# SCB_Connectors.net
KiCad netlist of a schematic drawn in Altium Designer
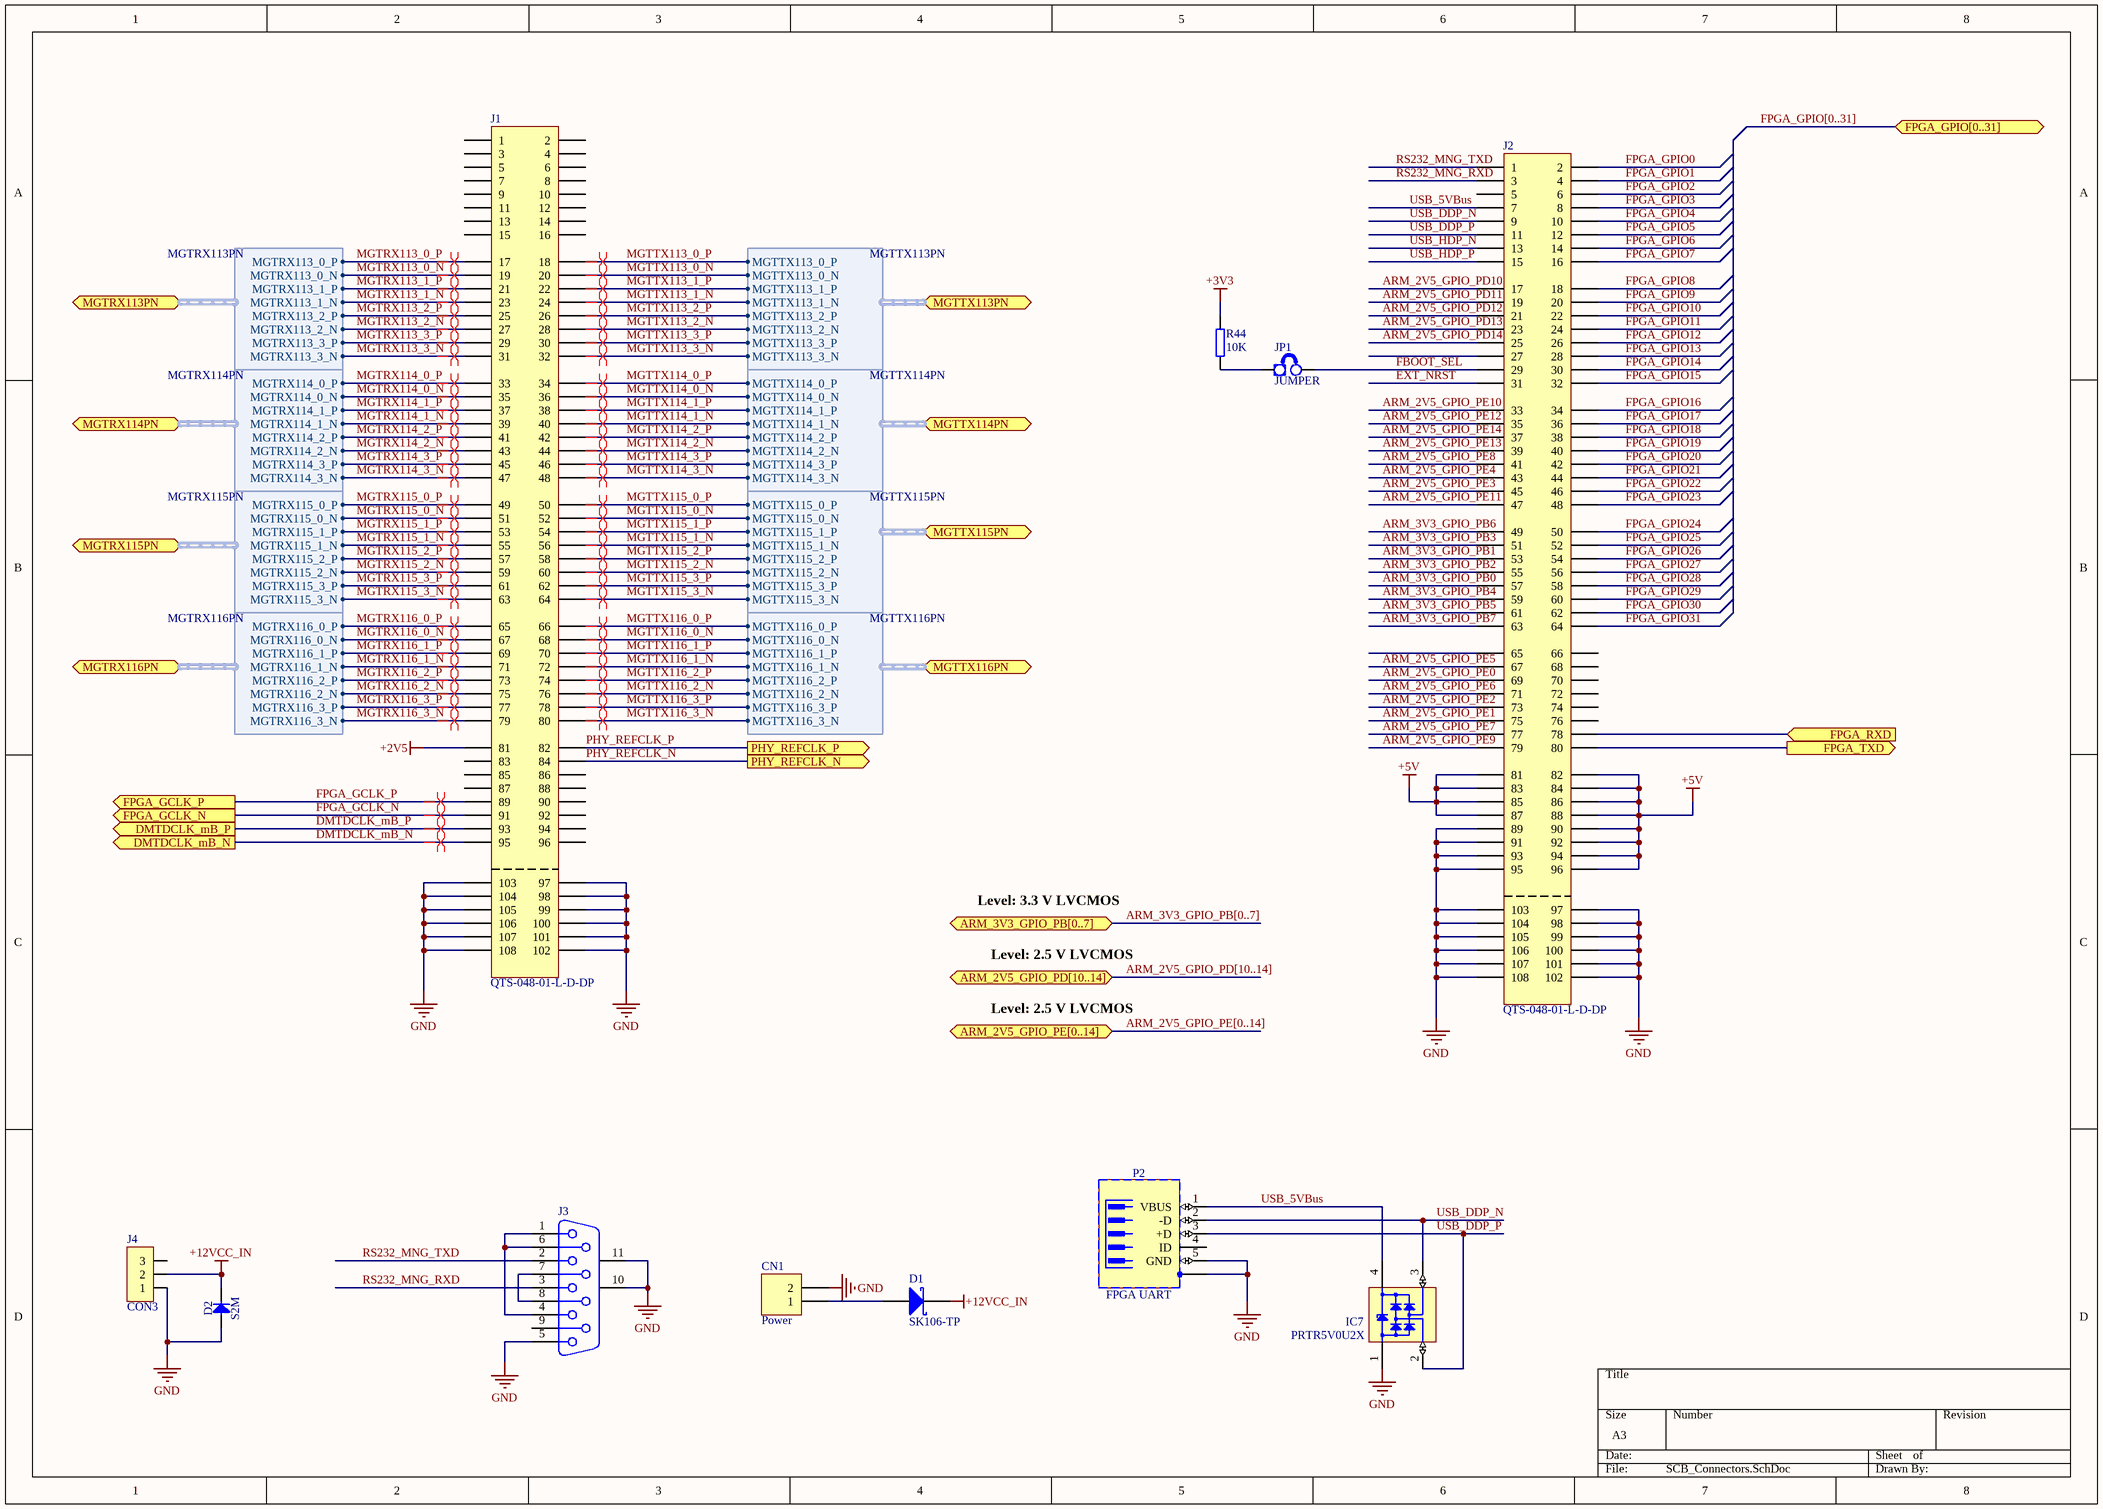
[diagram p0: SCB_Connectors.SchDoc]

(export (version "E")
  (design (tool "Eeschema 10.0.6"))
  (components
    (comp (ref "CN1")
      (value "Power")
      (footprint "TYCO_794120_1")
      (description "Header, 2-Pin")
      (fields (field (name "PUBLISHER") "Altium Limited"))
      (libsource (lib "Miscellaneous Connectors") (part "Header 2"))
    )
    (comp (ref "D1")
      (value "SK106-TP")
      (footprint "DIOM7959X262N")
      (description "Schottky Diode 10A 60V")
      (libsource (lib "wr_switch") (part "SK106-TP"))
    )
    (comp (ref "D2")
      (value "S2M")
      (footprint "7S_WR:DO-214AA/SMB")
      (description "Diode")
      (fields
        (field (name "VOLTAGE") "1000V")
        (field (name "POWER") "2A")
        (field (name "AUTHOR") "CERN DEM JLC")
      )
      (libsource (lib "ICs And Semiconductors") (part "Diode"))
    )
    (comp (ref "IC7")
      (value "PRTR5V0U2X")
      (footprint "7S_WR:SOT190P230X110-4N")
      (description "Ultra Low Capacitance Double Rail-to-Rail ESD Protection Diode")
      (fields
        (field (name "VOLTAGE") "5.5V")
        (field (name "MANUFACTURER") "PHILIPS NXP")
        (field (name "AUTHOR") "CERN DEM JLC")
      )
      (libsource (lib "wr_switch") (part "PRTR5V0U2X"))
    )
    (comp (ref "J1")
      (value "QTS-048-01-L-D-DP")
      (footprint "7S_WR:QTS-048-XX-X-D-DP-A")
      (description "High Speed Ground Plane Header")
      (libsource (lib "wr_switch") (part "QTS-048-01-L-D-DP"))
    )
    (comp (ref "J2")
      (value "QTS-048-01-L-D-DP")
      (footprint "7S_WR:QTS-048-XX-X-D-DP-A")
      (description "High Speed Ground Plane Header")
      (libsource (lib "wr_switch") (part "QTS-048-01-L-D-DP"))
    )
    (comp (ref "J3")
      (value "D Connector 9")
      (footprint "DSUB1.385-2H9")
      (description "Receptacle Assembly, 9 Position, Right Angle")
      (fields (field (name "PUBLISHER") "Altium Limited"))
      (libsource (lib "Miscellaneous Connectors") (part "D Connector 9"))
    )
    (comp (ref "J4")
      (value "CON3")
      (footprint "MOLEX_22-11-2032")
      (description "Connector")
      (libsource (lib "LIBRARY_SCH") (part "CON3"))
    )
    (comp (ref "JP1")
      (value "JUMPER")
      (footprint "footprints:con_1x2_1.27")
      (description "Jumper")
      (libsource (lib "LIBRARY_SCH") (part "JUMPER"))
    )
    (comp (ref "P2")
      (value "FPGA UART")
      (footprint "7S_WR:TYCO_1734035-1")
      (description "5 Pin + 1 Shield USB Receptacle")
      (fields
        (field (name "PART NUMBER") "TYCO_1734035-1")
        (field (name "MANUFACTURER") "TYCO ELECTRONICS")
        (field (name "AUTHOR") "CERN DEM JLC")
      )
      (libsource (lib "Connectors") (part "Connector USB 5 Pin + 1Shield"))
    )
    (comp (ref "R44")
      (value "10K")
      (footprint "0603")
      (description "SMD Resistor")
      (fields (field (name "TOLERANCE") "±1%"))
      (libsource (lib "wr_switch") (part "RES_SMD"))
    )
  )
  (nets
    (net (code "9") (name "+2V5") (class "Default")
      (node (ref "J1") (pin "81") (pinfunction "81_81") (pintype "passive"))
    )
    (net (code "10") (name "+3V3") (class "Default")
      (node (ref "R44") (pin "2") (pinfunction "2_2") (pintype "passive"))
    )
    (net (code "11") (name "+5V") (class "Default")
      (node (ref "J2") (pin "81") (pinfunction "81_81") (pintype "passive"))
      (node (ref "J2") (pin "82") (pinfunction "82_82") (pintype "passive"))
      (node (ref "J2") (pin "83") (pinfunction "83_83") (pintype "passive"))
      (node (ref "J2") (pin "84") (pinfunction "84_84") (pintype "passive"))
      (node (ref "J2") (pin "85") (pinfunction "85_85") (pintype "passive"))
      (node (ref "J2") (pin "86") (pinfunction "86_86") (pintype "passive"))
      (node (ref "J2") (pin "87") (pinfunction "87_87") (pintype "passive"))
      (node (ref "J2") (pin "88") (pinfunction "88_88") (pintype "passive"))
      (node (ref "J2") (pin "90") (pinfunction "90_90") (pintype "passive"))
      (node (ref "J2") (pin "92") (pinfunction "92_92") (pintype "passive"))
      (node (ref "J2") (pin "94") (pinfunction "94_94") (pintype "passive"))
      (node (ref "J2") (pin "96") (pinfunction "96_96") (pintype "passive"))
    )
    (net (code "12") (name "+12VCC_IN") (class "Default")
      (node (ref "D1") (pin "2") (pinfunction "K_2") (pintype "passive"))
      (node (ref "D2") (pin "1") (pinfunction "C_1") (pintype "passive"))
      (node (ref "J4") (pin "2") (pinfunction "2_2") (pintype "passive"))
    )
    (net (code "13") (name "/ARM_2V5_GPIO_PD10") (class "Default")
      (node (ref "J2") (pin "17") (pinfunction "17_17") (pintype "passive"))
    )
    (net (code "14") (name "/ARM_2V5_GPIO_PD11") (class "Default")
      (node (ref "J2") (pin "19") (pinfunction "19_19") (pintype "passive"))
    )
    (net (code "15") (name "/ARM_2V5_GPIO_PD12") (class "Default")
      (node (ref "J2") (pin "21") (pinfunction "21_21") (pintype "passive"))
    )
    (net (code "16") (name "/ARM_2V5_GPIO_PD13") (class "Default")
      (node (ref "J2") (pin "23") (pinfunction "23_23") (pintype "passive"))
    )
    (net (code "17") (name "/ARM_2V5_GPIO_PD14") (class "Default")
      (node (ref "J2") (pin "25") (pinfunction "25_25") (pintype "passive"))
    )
    (net (code "19") (name "/ARM_2V5_GPIO_PE0") (class "Default")
      (node (ref "J2") (pin "69") (pinfunction "69_69") (pintype "passive"))
    )
    (net (code "20") (name "/ARM_2V5_GPIO_PE1") (class "Default")
      (node (ref "J2") (pin "75") (pinfunction "75_75") (pintype "passive"))
    )
    (net (code "21") (name "/ARM_2V5_GPIO_PE2") (class "Default")
      (node (ref "J2") (pin "73") (pinfunction "73_73") (pintype "passive"))
    )
    (net (code "22") (name "/ARM_2V5_GPIO_PE3") (class "Default")
      (node (ref "J2") (pin "45") (pinfunction "45_45") (pintype "passive"))
    )
    (net (code "23") (name "/ARM_2V5_GPIO_PE4") (class "Default")
      (node (ref "J2") (pin "43") (pinfunction "43_43") (pintype "passive"))
    )
    (net (code "24") (name "/ARM_2V5_GPIO_PE5") (class "Default")
      (node (ref "J2") (pin "67") (pinfunction "67_67") (pintype "passive"))
    )
    (net (code "25") (name "/ARM_2V5_GPIO_PE6") (class "Default")
      (node (ref "J2") (pin "71") (pinfunction "71_71") (pintype "passive"))
    )
    (net (code "26") (name "/ARM_2V5_GPIO_PE7") (class "Default")
      (node (ref "J2") (pin "77") (pinfunction "77_77") (pintype "passive"))
    )
    (net (code "27") (name "/ARM_2V5_GPIO_PE8") (class "Default")
      (node (ref "J2") (pin "41") (pinfunction "41_41") (pintype "passive"))
    )
    (net (code "28") (name "/ARM_2V5_GPIO_PE9") (class "Default")
      (node (ref "J2") (pin "79") (pinfunction "79_79") (pintype "passive"))
    )
    (net (code "29") (name "/ARM_2V5_GPIO_PE10") (class "Default")
      (node (ref "J2") (pin "33") (pinfunction "33_33") (pintype "passive"))
    )
    (net (code "30") (name "/ARM_2V5_GPIO_PE11") (class "Default")
      (node (ref "J2") (pin "47") (pinfunction "47_47") (pintype "passive"))
    )
    (net (code "31") (name "/ARM_2V5_GPIO_PE12") (class "Default")
      (node (ref "J2") (pin "35") (pinfunction "35_35") (pintype "passive"))
    )
    (net (code "32") (name "/ARM_2V5_GPIO_PE13") (class "Default")
      (node (ref "J2") (pin "39") (pinfunction "39_39") (pintype "passive"))
    )
    (net (code "33") (name "/ARM_2V5_GPIO_PE14") (class "Default")
      (node (ref "J2") (pin "37") (pinfunction "37_37") (pintype "passive"))
    )
    (net (code "35") (name "/ARM_3V3_GPIO_PB0") (class "Default")
      (node (ref "J2") (pin "57") (pinfunction "57_57") (pintype "passive"))
    )
    (net (code "36") (name "/ARM_3V3_GPIO_PB1") (class "Default")
      (node (ref "J2") (pin "53") (pinfunction "53_53") (pintype "passive"))
    )
    (net (code "37") (name "/ARM_3V3_GPIO_PB2") (class "Default")
      (node (ref "J2") (pin "55") (pinfunction "55_55") (pintype "passive"))
    )
    (net (code "38") (name "/ARM_3V3_GPIO_PB3") (class "Default")
      (node (ref "J2") (pin "51") (pinfunction "51_51") (pintype "passive"))
    )
    (net (code "39") (name "/ARM_3V3_GPIO_PB4") (class "Default")
      (node (ref "J2") (pin "59") (pinfunction "59_59") (pintype "passive"))
    )
    (net (code "40") (name "/ARM_3V3_GPIO_PB5") (class "Default")
      (node (ref "J2") (pin "61") (pinfunction "61_61") (pintype "passive"))
    )
    (net (code "41") (name "/ARM_3V3_GPIO_PB6") (class "Default")
      (node (ref "J2") (pin "49") (pinfunction "49_49") (pintype "passive"))
    )
    (net (code "42") (name "/ARM_3V3_GPIO_PB7") (class "Default")
      (node (ref "J2") (pin "63") (pinfunction "63_63") (pintype "passive"))
    )
    (net (code "44") (name "/DMTDCLK_mB_N") (class "Default")
      (node (ref "J1") (pin "95") (pinfunction "95_95") (pintype "passive"))
    )
    (net (code "45") (name "/DMTDCLK_mB_P") (class "Default")
      (node (ref "J1") (pin "93") (pinfunction "93_93") (pintype "passive"))
    )
    (net (code "46") (name "/EXT_NRST") (class "Default")
      (node (ref "J2") (pin "31") (pinfunction "31_31") (pintype "passive"))
    )
    (net (code "47") (name "/FBOOT_SEL") (class "Default")
      (node (ref "J2") (pin "29") (pinfunction "29_29") (pintype "passive"))
      (node (ref "JP1") (pin "2") (pinfunction "E2_2") (pintype "passive"))
    )
    (net (code "48") (name "/FPGA_GCLK_N") (class "Default")
      (node (ref "J1") (pin "91") (pinfunction "91_91") (pintype "passive"))
    )
    (net (code "49") (name "/FPGA_GCLK_P") (class "Default")
      (node (ref "J1") (pin "89") (pinfunction "89_89") (pintype "passive"))
    )
    (net (code "50") (name "/FPGA_GPIO0") (class "Default")
      (node (ref "J2") (pin "2") (pinfunction "2_2") (pintype "passive"))
    )
    (net (code "51") (name "/FPGA_GPIO1") (class "Default")
      (node (ref "J2") (pin "4") (pinfunction "4_4") (pintype "passive"))
    )
    (net (code "52") (name "/FPGA_GPIO2") (class "Default")
      (node (ref "J2") (pin "6") (pinfunction "6_6") (pintype "passive"))
    )
    (net (code "53") (name "/FPGA_GPIO3") (class "Default")
      (node (ref "J2") (pin "8") (pinfunction "8_8") (pintype "passive"))
    )
    (net (code "54") (name "/FPGA_GPIO4") (class "Default")
      (node (ref "J2") (pin "10") (pinfunction "10_10") (pintype "passive"))
    )
    (net (code "55") (name "/FPGA_GPIO5") (class "Default")
      (node (ref "J2") (pin "12") (pinfunction "12_12") (pintype "passive"))
    )
    (net (code "56") (name "/FPGA_GPIO6") (class "Default")
      (node (ref "J2") (pin "14") (pinfunction "14_14") (pintype "passive"))
    )
    (net (code "57") (name "/FPGA_GPIO7") (class "Default")
      (node (ref "J2") (pin "16") (pinfunction "16_16") (pintype "passive"))
    )
    (net (code "58") (name "/FPGA_GPIO8") (class "Default")
      (node (ref "J2") (pin "18") (pinfunction "18_18") (pintype "passive"))
    )
    (net (code "59") (name "/FPGA_GPIO9") (class "Default")
      (node (ref "J2") (pin "20") (pinfunction "20_20") (pintype "passive"))
    )
    (net (code "60") (name "/FPGA_GPIO10") (class "Default")
      (node (ref "J2") (pin "22") (pinfunction "22_22") (pintype "passive"))
    )
    (net (code "61") (name "/FPGA_GPIO11") (class "Default")
      (node (ref "J2") (pin "24") (pinfunction "24_24") (pintype "passive"))
    )
    (net (code "62") (name "/FPGA_GPIO12") (class "Default")
      (node (ref "J2") (pin "26") (pinfunction "26_26") (pintype "passive"))
    )
    (net (code "63") (name "/FPGA_GPIO13") (class "Default")
      (node (ref "J2") (pin "28") (pinfunction "28_28") (pintype "passive"))
    )
    (net (code "64") (name "/FPGA_GPIO14") (class "Default")
      (node (ref "J2") (pin "30") (pinfunction "30_30") (pintype "passive"))
    )
    (net (code "65") (name "/FPGA_GPIO15") (class "Default")
      (node (ref "J2") (pin "32") (pinfunction "32_32") (pintype "passive"))
    )
    (net (code "66") (name "/FPGA_GPIO16") (class "Default")
      (node (ref "J2") (pin "34") (pinfunction "34_34") (pintype "passive"))
    )
    (net (code "67") (name "/FPGA_GPIO17") (class "Default")
      (node (ref "J2") (pin "36") (pinfunction "36_36") (pintype "passive"))
    )
    (net (code "68") (name "/FPGA_GPIO18") (class "Default")
      (node (ref "J2") (pin "38") (pinfunction "38_38") (pintype "passive"))
    )
    (net (code "69") (name "/FPGA_GPIO19") (class "Default")
      (node (ref "J2") (pin "40") (pinfunction "40_40") (pintype "passive"))
    )
    (net (code "70") (name "/FPGA_GPIO20") (class "Default")
      (node (ref "J2") (pin "42") (pinfunction "42_42") (pintype "passive"))
    )
    (net (code "71") (name "/FPGA_GPIO21") (class "Default")
      (node (ref "J2") (pin "44") (pinfunction "44_44") (pintype "passive"))
    )
    (net (code "72") (name "/FPGA_GPIO22") (class "Default")
      (node (ref "J2") (pin "46") (pinfunction "46_46") (pintype "passive"))
    )
    (net (code "73") (name "/FPGA_GPIO23") (class "Default")
      (node (ref "J2") (pin "48") (pinfunction "48_48") (pintype "passive"))
    )
    (net (code "74") (name "/FPGA_GPIO24") (class "Default")
      (node (ref "J2") (pin "50") (pinfunction "50_50") (pintype "passive"))
    )
    (net (code "75") (name "/FPGA_GPIO25") (class "Default")
      (node (ref "J2") (pin "52") (pinfunction "52_52") (pintype "passive"))
    )
    (net (code "76") (name "/FPGA_GPIO26") (class "Default")
      (node (ref "J2") (pin "54") (pinfunction "54_54") (pintype "passive"))
    )
    (net (code "77") (name "/FPGA_GPIO27") (class "Default")
      (node (ref "J2") (pin "56") (pinfunction "56_56") (pintype "passive"))
    )
    (net (code "78") (name "/FPGA_GPIO28") (class "Default")
      (node (ref "J2") (pin "58") (pinfunction "58_58") (pintype "passive"))
    )
    (net (code "79") (name "/FPGA_GPIO29") (class "Default")
      (node (ref "J2") (pin "60") (pinfunction "60_60") (pintype "passive"))
    )
    (net (code "80") (name "/FPGA_GPIO30") (class "Default")
      (node (ref "J2") (pin "62") (pinfunction "62_62") (pintype "passive"))
    )
    (net (code "81") (name "/FPGA_GPIO31") (class "Default")
      (node (ref "J2") (pin "64") (pinfunction "64_64") (pintype "passive"))
    )
    (net (code "83") (name "/FPGA_RXD") (class "Default")
      (node (ref "J2") (pin "78") (pinfunction "78_78") (pintype "passive"))
    )
    (net (code "84") (name "/FPGA_TXD") (class "Default")
      (node (ref "J2") (pin "80") (pinfunction "80_80") (pintype "passive"))
    )
    (net (code "86") (name "/MGTRX113_0_N") (class "Default")
      (node (ref "J1") (pin "19") (pinfunction "19_19") (pintype "passive"))
    )
    (net (code "87") (name "/MGTRX113_0_P") (class "Default")
      (node (ref "J1") (pin "17") (pinfunction "17_17") (pintype "passive"))
    )
    (net (code "88") (name "/MGTRX113_1_N") (class "Default")
      (node (ref "J1") (pin "23") (pinfunction "23_23") (pintype "passive"))
    )
    (net (code "89") (name "/MGTRX113_1_P") (class "Default")
      (node (ref "J1") (pin "21") (pinfunction "21_21") (pintype "passive"))
    )
    (net (code "90") (name "/MGTRX113_2_N") (class "Default")
      (node (ref "J1") (pin "27") (pinfunction "27_27") (pintype "passive"))
    )
    (net (code "91") (name "/MGTRX113_2_P") (class "Default")
      (node (ref "J1") (pin "25") (pinfunction "25_25") (pintype "passive"))
    )
    (net (code "92") (name "/MGTRX113_3_N") (class "Default")
      (node (ref "J1") (pin "31") (pinfunction "31_31") (pintype "passive"))
    )
    (net (code "93") (name "/MGTRX113_3_P") (class "Default")
      (node (ref "J1") (pin "29") (pinfunction "29_29") (pintype "passive"))
    )
    (net (code "94") (name "/MGTRX114_0_N") (class "Default")
      (node (ref "J1") (pin "35") (pinfunction "35_35") (pintype "passive"))
    )
    (net (code "95") (name "/MGTRX114_0_P") (class "Default")
      (node (ref "J1") (pin "33") (pinfunction "33_33") (pintype "passive"))
    )
    (net (code "96") (name "/MGTRX114_1_N") (class "Default")
      (node (ref "J1") (pin "39") (pinfunction "39_39") (pintype "passive"))
    )
    (net (code "97") (name "/MGTRX114_1_P") (class "Default")
      (node (ref "J1") (pin "37") (pinfunction "37_37") (pintype "passive"))
    )
    (net (code "98") (name "/MGTRX114_2_N") (class "Default")
      (node (ref "J1") (pin "43") (pinfunction "43_43") (pintype "passive"))
    )
    (net (code "99") (name "/MGTRX114_2_P") (class "Default")
      (node (ref "J1") (pin "41") (pinfunction "41_41") (pintype "passive"))
    )
    (net (code "100") (name "/MGTRX114_3_N") (class "Default")
      (node (ref "J1") (pin "47") (pinfunction "47_47") (pintype "passive"))
    )
    (net (code "101") (name "/MGTRX114_3_P") (class "Default")
      (node (ref "J1") (pin "45") (pinfunction "45_45") (pintype "passive"))
    )
    (net (code "102") (name "/MGTRX115_0_N") (class "Default")
      (node (ref "J1") (pin "51") (pinfunction "51_51") (pintype "passive"))
    )
    (net (code "103") (name "/MGTRX115_0_P") (class "Default")
      (node (ref "J1") (pin "49") (pinfunction "49_49") (pintype "passive"))
    )
    (net (code "104") (name "/MGTRX115_1_N") (class "Default")
      (node (ref "J1") (pin "55") (pinfunction "55_55") (pintype "passive"))
    )
    (net (code "105") (name "/MGTRX115_1_P") (class "Default")
      (node (ref "J1") (pin "53") (pinfunction "53_53") (pintype "passive"))
    )
    (net (code "106") (name "/MGTRX115_2_N") (class "Default")
      (node (ref "J1") (pin "59") (pinfunction "59_59") (pintype "passive"))
    )
    (net (code "107") (name "/MGTRX115_2_P") (class "Default")
      (node (ref "J1") (pin "57") (pinfunction "57_57") (pintype "passive"))
    )
    (net (code "108") (name "/MGTRX115_3_N") (class "Default")
      (node (ref "J1") (pin "63") (pinfunction "63_63") (pintype "passive"))
    )
    (net (code "109") (name "/MGTRX115_3_P") (class "Default")
      (node (ref "J1") (pin "61") (pinfunction "61_61") (pintype "passive"))
    )
    (net (code "110") (name "/MGTRX116_0_N") (class "Default")
      (node (ref "J1") (pin "67") (pinfunction "67_67") (pintype "passive"))
    )
    (net (code "111") (name "/MGTRX116_0_P") (class "Default")
      (node (ref "J1") (pin "65") (pinfunction "65_65") (pintype "passive"))
    )
    (net (code "112") (name "/MGTRX116_1_N") (class "Default")
      (node (ref "J1") (pin "71") (pinfunction "71_71") (pintype "passive"))
    )
    (net (code "113") (name "/MGTRX116_1_P") (class "Default")
      (node (ref "J1") (pin "69") (pinfunction "69_69") (pintype "passive"))
    )
    (net (code "114") (name "/MGTRX116_2_N") (class "Default")
      (node (ref "J1") (pin "75") (pinfunction "75_75") (pintype "passive"))
    )
    (net (code "115") (name "/MGTRX116_2_P") (class "Default")
      (node (ref "J1") (pin "73") (pinfunction "73_73") (pintype "passive"))
    )
    (net (code "116") (name "/MGTRX116_3_N") (class "Default")
      (node (ref "J1") (pin "79") (pinfunction "79_79") (pintype "passive"))
    )
    (net (code "117") (name "/MGTRX116_3_P") (class "Default")
      (node (ref "J1") (pin "77") (pinfunction "77_77") (pintype "passive"))
    )
    (net (code "118") (name "/MGTTX113_0_N") (class "Default")
      (node (ref "J1") (pin "20") (pinfunction "20_20") (pintype "passive"))
    )
    (net (code "119") (name "/MGTTX113_0_P") (class "Default")
      (node (ref "J1") (pin "18") (pinfunction "18_18") (pintype "passive"))
    )
    (net (code "120") (name "/MGTTX113_1_N") (class "Default")
      (node (ref "J1") (pin "24") (pinfunction "24_24") (pintype "passive"))
    )
    (net (code "121") (name "/MGTTX113_1_P") (class "Default")
      (node (ref "J1") (pin "22") (pinfunction "22_22") (pintype "passive"))
    )
    (net (code "122") (name "/MGTTX113_2_N") (class "Default")
      (node (ref "J1") (pin "28") (pinfunction "28_28") (pintype "passive"))
    )
    (net (code "123") (name "/MGTTX113_2_P") (class "Default")
      (node (ref "J1") (pin "26") (pinfunction "26_26") (pintype "passive"))
    )
    (net (code "124") (name "/MGTTX113_3_N") (class "Default")
      (node (ref "J1") (pin "32") (pinfunction "32_32") (pintype "passive"))
    )
    (net (code "125") (name "/MGTTX113_3_P") (class "Default")
      (node (ref "J1") (pin "30") (pinfunction "30_30") (pintype "passive"))
    )
    (net (code "126") (name "/MGTTX114_0_N") (class "Default")
      (node (ref "J1") (pin "36") (pinfunction "36_36") (pintype "passive"))
    )
    (net (code "127") (name "/MGTTX114_0_P") (class "Default")
      (node (ref "J1") (pin "34") (pinfunction "34_34") (pintype "passive"))
    )
    (net (code "128") (name "/MGTTX114_1_N") (class "Default")
      (node (ref "J1") (pin "40") (pinfunction "40_40") (pintype "passive"))
    )
    (net (code "129") (name "/MGTTX114_1_P") (class "Default")
      (node (ref "J1") (pin "38") (pinfunction "38_38") (pintype "passive"))
    )
    (net (code "130") (name "/MGTTX114_2_N") (class "Default")
      (node (ref "J1") (pin "44") (pinfunction "44_44") (pintype "passive"))
    )
    (net (code "131") (name "/MGTTX114_2_P") (class "Default")
      (node (ref "J1") (pin "42") (pinfunction "42_42") (pintype "passive"))
    )
    (net (code "132") (name "/MGTTX114_3_N") (class "Default")
      (node (ref "J1") (pin "48") (pinfunction "48_48") (pintype "passive"))
    )
    (net (code "133") (name "/MGTTX114_3_P") (class "Default")
      (node (ref "J1") (pin "46") (pinfunction "46_46") (pintype "passive"))
    )
    (net (code "134") (name "/MGTTX115_0_N") (class "Default")
      (node (ref "J1") (pin "52") (pinfunction "52_52") (pintype "passive"))
    )
    (net (code "135") (name "/MGTTX115_0_P") (class "Default")
      (node (ref "J1") (pin "50") (pinfunction "50_50") (pintype "passive"))
    )
    (net (code "136") (name "/MGTTX115_1_N") (class "Default")
      (node (ref "J1") (pin "56") (pinfunction "56_56") (pintype "passive"))
    )
    (net (code "137") (name "/MGTTX115_1_P") (class "Default")
      (node (ref "J1") (pin "54") (pinfunction "54_54") (pintype "passive"))
    )
    (net (code "138") (name "/MGTTX115_2_N") (class "Default")
      (node (ref "J1") (pin "60") (pinfunction "60_60") (pintype "passive"))
    )
    (net (code "139") (name "/MGTTX115_2_P") (class "Default")
      (node (ref "J1") (pin "58") (pinfunction "58_58") (pintype "passive"))
    )
    (net (code "140") (name "/MGTTX115_3_N") (class "Default")
      (node (ref "J1") (pin "64") (pinfunction "64_64") (pintype "passive"))
    )
    (net (code "141") (name "/MGTTX115_3_P") (class "Default")
      (node (ref "J1") (pin "62") (pinfunction "62_62") (pintype "passive"))
    )
    (net (code "142") (name "/MGTTX116_0_N") (class "Default")
      (node (ref "J1") (pin "68") (pinfunction "68_68") (pintype "passive"))
    )
    (net (code "143") (name "/MGTTX116_0_P") (class "Default")
      (node (ref "J1") (pin "66") (pinfunction "66_66") (pintype "passive"))
    )
    (net (code "144") (name "/MGTTX116_1_N") (class "Default")
      (node (ref "J1") (pin "72") (pinfunction "72_72") (pintype "passive"))
    )
    (net (code "145") (name "/MGTTX116_1_P") (class "Default")
      (node (ref "J1") (pin "70") (pinfunction "70_70") (pintype "passive"))
    )
    (net (code "146") (name "/MGTTX116_2_N") (class "Default")
      (node (ref "J1") (pin "76") (pinfunction "76_76") (pintype "passive"))
    )
    (net (code "147") (name "/MGTTX116_2_P") (class "Default")
      (node (ref "J1") (pin "74") (pinfunction "74_74") (pintype "passive"))
    )
    (net (code "148") (name "/MGTTX116_3_N") (class "Default")
      (node (ref "J1") (pin "80") (pinfunction "80_80") (pintype "passive"))
    )
    (net (code "149") (name "/MGTTX116_3_P") (class "Default")
      (node (ref "J1") (pin "78") (pinfunction "78_78") (pintype "passive"))
    )
    (net (code "150") (name "/PHY_REFCLK_N") (class "Default")
      (node (ref "J1") (pin "84") (pinfunction "84_84") (pintype "passive"))
    )
    (net (code "151") (name "/PHY_REFCLK_P") (class "Default")
      (node (ref "J1") (pin "82") (pinfunction "82_82") (pintype "passive"))
    )
    (net (code "152") (name "/RS232_MNG_RXD") (class "Default")
      (node (ref "J2") (pin "3") (pinfunction "3_3") (pintype "passive"))
      (node (ref "J3") (pin "3") (pinfunction "3_3") (pintype "passive"))
    )
    (net (code "153") (name "/RS232_MNG_TXD") (class "Default")
      (node (ref "J2") (pin "1") (pinfunction "1_1") (pintype "passive"))
      (node (ref "J3") (pin "2") (pinfunction "2_2") (pintype "passive"))
    )
    (net (code "154") (name "/USB_5VBus") (class "Default")
      (node (ref "IC7") (pin "4") (pinfunction "VCC_4") (pintype "power_in"))
      (node (ref "J2") (pin "7") (pinfunction "7_7") (pintype "passive"))
      (node (ref "P2") (pin "1") (pinfunction "VBUS_1") (pintype "bidirectional"))
    )
    (net (code "155") (name "/USB_DDP_N") (class "Default")
      (node (ref "IC7") (pin "3") (pinfunction "I/O2_3") (pintype "bidirectional"))
      (node (ref "J2") (pin "9") (pinfunction "9_9") (pintype "passive"))
      (node (ref "P2") (pin "2") (pinfunction "-D_2") (pintype "bidirectional"))
    )
    (net (code "156") (name "/USB_DDP_P") (class "Default")
      (node (ref "IC7") (pin "2") (pinfunction "I/O1_2") (pintype "bidirectional"))
      (node (ref "J2") (pin "11") (pinfunction "11_11") (pintype "passive"))
      (node (ref "P2") (pin "3") (pinfunction "+D_3") (pintype "bidirectional"))
    )
    (net (code "157") (name "/USB_HDP_N") (class "Default")
      (node (ref "J2") (pin "13") (pinfunction "13_13") (pintype "passive"))
    )
    (net (code "158") (name "/USB_HDP_P") (class "Default")
      (node (ref "J2") (pin "15") (pinfunction "15_15") (pintype "passive"))
    )
    (net (code "166") (name "GND") (class "Default")
      (node (ref "CN1") (pin "2") (pinfunction "2_2") (pintype "passive"))
      (node (ref "D2") (pin "2") (pinfunction "A_2") (pintype "passive"))
      (node (ref "IC7") (pin "1") (pinfunction "GND_1") (pintype "power_in"))
      (node (ref "J1") (pin "100") (pinfunction "100_100") (pintype "passive"))
      (node (ref "J1") (pin "101") (pinfunction "101_101") (pintype "passive"))
      (node (ref "J1") (pin "102") (pinfunction "102_102") (pintype "passive"))
      (node (ref "J1") (pin "103") (pinfunction "103_103") (pintype "passive"))
      (node (ref "J1") (pin "104") (pinfunction "104_104") (pintype "passive"))
      (node (ref "J1") (pin "105") (pinfunction "105_105") (pintype "passive"))
      (node (ref "J1") (pin "106") (pinfunction "106_106") (pintype "passive"))
      (node (ref "J1") (pin "107") (pinfunction "107_107") (pintype "passive"))
      (node (ref "J1") (pin "108") (pinfunction "108_108") (pintype "passive"))
      (node (ref "J1") (pin "97") (pinfunction "97_97") (pintype "passive"))
      (node (ref "J1") (pin "98") (pinfunction "98_98") (pintype "passive"))
      (node (ref "J1") (pin "99") (pinfunction "99_99") (pintype "passive"))
      (node (ref "J2") (pin "100") (pinfunction "100_100") (pintype "passive"))
      (node (ref "J2") (pin "101") (pinfunction "101_101") (pintype "passive"))
      (node (ref "J2") (pin "102") (pinfunction "102_102") (pintype "passive"))
      (node (ref "J2") (pin "103") (pinfunction "103_103") (pintype "passive"))
      (node (ref "J2") (pin "104") (pinfunction "104_104") (pintype "passive"))
      (node (ref "J2") (pin "105") (pinfunction "105_105") (pintype "passive"))
      (node (ref "J2") (pin "106") (pinfunction "106_106") (pintype "passive"))
      (node (ref "J2") (pin "107") (pinfunction "107_107") (pintype "passive"))
      (node (ref "J2") (pin "108") (pinfunction "108_108") (pintype "passive"))
      (node (ref "J2") (pin "89") (pinfunction "89_89") (pintype "passive"))
      (node (ref "J2") (pin "91") (pinfunction "91_91") (pintype "passive"))
      (node (ref "J2") (pin "93") (pinfunction "93_93") (pintype "passive"))
      (node (ref "J2") (pin "95") (pinfunction "95_95") (pintype "passive"))
      (node (ref "J2") (pin "97") (pinfunction "97_97") (pintype "passive"))
      (node (ref "J2") (pin "98") (pinfunction "98_98") (pintype "passive"))
      (node (ref "J2") (pin "99") (pinfunction "99_99") (pintype "passive"))
      (node (ref "J3") (pin "10") (pinfunction "MH1_10") (pintype "passive"))
      (node (ref "J3") (pin "11") (pinfunction "MH2_11") (pintype "passive"))
      (node (ref "J3") (pin "5") (pinfunction "5_5") (pintype "passive"))
      (node (ref "J4") (pin "1") (pinfunction "1_1") (pintype "passive"))
      (node (ref "P2") (pin "5") (pinfunction "GND_5") (pintype "bidirectional"))
      (node (ref "P2") (pin "6") (pinfunction "SH_6") (pintype "power_in"))
    )
    (net (code "167") (name "Net-(D1-A)") (class "Default")
      (node (ref "CN1") (pin "1") (pinfunction "1_1") (pintype "passive"))
      (node (ref "D1") (pin "1") (pinfunction "A_1") (pintype "passive"))
    )
    (net (code "168") (name "Net-(J3-Pad1)") (class "Default")
      (node (ref "J3") (pin "1") (pinfunction "1_1") (pintype "passive"))
      (node (ref "J3") (pin "4") (pinfunction "4_4") (pintype "passive"))
      (node (ref "J3") (pin "6") (pinfunction "6_6") (pintype "passive"))
    )
    (net (code "169") (name "Net-(J3-Pad7)") (class "Default")
      (node (ref "J3") (pin "7") (pinfunction "7_7") (pintype "passive"))
      (node (ref "J3") (pin "8") (pinfunction "8_8") (pintype "passive"))
    )
    (net (code "170") (name "Net-(JP1-E1)") (class "Default")
      (node (ref "JP1") (pin "1") (pinfunction "E1_1") (pintype "passive"))
      (node (ref "R44") (pin "1") (pinfunction "1_1") (pintype "passive"))
    )
    (net (code "171") (name "unconnected-(J1-Pad1)") (class "Default")
      (node (ref "J1") (pin "1") (pinfunction "1_1") (pintype "passive"))
    )
    (net (code "172") (name "unconnected-(J1-Pad2)") (class "Default")
      (node (ref "J1") (pin "2") (pinfunction "2_2") (pintype "passive"))
    )
    (net (code "173") (name "unconnected-(J1-Pad3)") (class "Default")
      (node (ref "J1") (pin "3") (pinfunction "3_3") (pintype "passive"))
    )
    (net (code "174") (name "unconnected-(J1-Pad4)") (class "Default")
      (node (ref "J1") (pin "4") (pinfunction "4_4") (pintype "passive"))
    )
    (net (code "175") (name "unconnected-(J1-Pad5)") (class "Default")
      (node (ref "J1") (pin "5") (pinfunction "5_5") (pintype "passive"))
    )
    (net (code "176") (name "unconnected-(J1-Pad6)") (class "Default")
      (node (ref "J1") (pin "6") (pinfunction "6_6") (pintype "passive"))
    )
    (net (code "177") (name "unconnected-(J1-Pad7)") (class "Default")
      (node (ref "J1") (pin "7") (pinfunction "7_7") (pintype "passive"))
    )
    (net (code "178") (name "unconnected-(J1-Pad8)") (class "Default")
      (node (ref "J1") (pin "8") (pinfunction "8_8") (pintype "passive"))
    )
    (net (code "179") (name "unconnected-(J1-Pad9)") (class "Default")
      (node (ref "J1") (pin "9") (pinfunction "9_9") (pintype "passive"))
    )
    (net (code "180") (name "unconnected-(J1-Pad10)") (class "Default")
      (node (ref "J1") (pin "10") (pinfunction "10_10") (pintype "passive"))
    )
    (net (code "181") (name "unconnected-(J1-Pad11)") (class "Default")
      (node (ref "J1") (pin "11") (pinfunction "11_11") (pintype "passive"))
    )
    (net (code "182") (name "unconnected-(J1-Pad12)") (class "Default")
      (node (ref "J1") (pin "12") (pinfunction "12_12") (pintype "passive"))
    )
    (net (code "183") (name "unconnected-(J1-Pad13)") (class "Default")
      (node (ref "J1") (pin "13") (pinfunction "13_13") (pintype "passive"))
    )
    (net (code "184") (name "unconnected-(J1-Pad14)") (class "Default")
      (node (ref "J1") (pin "14") (pinfunction "14_14") (pintype "passive"))
    )
    (net (code "185") (name "unconnected-(J1-Pad15)") (class "Default")
      (node (ref "J1") (pin "15") (pinfunction "15_15") (pintype "passive"))
    )
    (net (code "186") (name "unconnected-(J1-Pad16)") (class "Default")
      (node (ref "J1") (pin "16") (pinfunction "16_16") (pintype "passive"))
    )
    (net (code "187") (name "unconnected-(J1-Pad83)") (class "Default")
      (node (ref "J1") (pin "83") (pinfunction "83_83") (pintype "passive"))
    )
    (net (code "188") (name "unconnected-(J1-Pad85)") (class "Default")
      (node (ref "J1") (pin "85") (pinfunction "85_85") (pintype "passive"))
    )
    (net (code "189") (name "unconnected-(J1-Pad86)") (class "Default")
      (node (ref "J1") (pin "86") (pinfunction "86_86") (pintype "passive"))
    )
    (net (code "190") (name "unconnected-(J1-Pad87)") (class "Default")
      (node (ref "J1") (pin "87") (pinfunction "87_87") (pintype "passive"))
    )
    (net (code "191") (name "unconnected-(J1-Pad88)") (class "Default")
      (node (ref "J1") (pin "88") (pinfunction "88_88") (pintype "passive"))
    )
    (net (code "192") (name "unconnected-(J1-Pad90)") (class "Default")
      (node (ref "J1") (pin "90") (pinfunction "90_90") (pintype "passive"))
    )
    (net (code "193") (name "unconnected-(J1-Pad92)") (class "Default")
      (node (ref "J1") (pin "92") (pinfunction "92_92") (pintype "passive"))
    )
    (net (code "194") (name "unconnected-(J1-Pad94)") (class "Default")
      (node (ref "J1") (pin "94") (pinfunction "94_94") (pintype "passive"))
    )
    (net (code "195") (name "unconnected-(J1-Pad96)") (class "Default")
      (node (ref "J1") (pin "96") (pinfunction "96_96") (pintype "passive"))
    )
    (net (code "196") (name "unconnected-(J2-Pad5)") (class "Default")
      (node (ref "J2") (pin "5") (pinfunction "5_5") (pintype "passive"))
    )
    (net (code "197") (name "unconnected-(J2-Pad27)") (class "Default")
      (node (ref "J2") (pin "27") (pinfunction "27_27") (pintype "passive"))
    )
    (net (code "198") (name "unconnected-(J2-Pad65)") (class "Default")
      (node (ref "J2") (pin "65") (pinfunction "65_65") (pintype "passive"))
    )
    (net (code "199") (name "unconnected-(J2-Pad66)") (class "Default")
      (node (ref "J2") (pin "66") (pinfunction "66_66") (pintype "passive"))
    )
    (net (code "200") (name "unconnected-(J2-Pad68)") (class "Default")
      (node (ref "J2") (pin "68") (pinfunction "68_68") (pintype "passive"))
    )
    (net (code "201") (name "unconnected-(J2-Pad70)") (class "Default")
      (node (ref "J2") (pin "70") (pinfunction "70_70") (pintype "passive"))
    )
    (net (code "202") (name "unconnected-(J2-Pad72)") (class "Default")
      (node (ref "J2") (pin "72") (pinfunction "72_72") (pintype "passive"))
    )
    (net (code "203") (name "unconnected-(J2-Pad74)") (class "Default")
      (node (ref "J2") (pin "74") (pinfunction "74_74") (pintype "passive"))
    )
    (net (code "204") (name "unconnected-(J2-Pad76)") (class "Default")
      (node (ref "J2") (pin "76") (pinfunction "76_76") (pintype "passive"))
    )
    (net (code "205") (name "unconnected-(J3-Pad9)") (class "Default")
      (node (ref "J3") (pin "9") (pinfunction "9_9") (pintype "passive"))
    )
    (net (code "206") (name "unconnected-(J4-Pad3)") (class "Default")
      (node (ref "J4") (pin "3") (pinfunction "3_3") (pintype "passive"))
    )
    (net (code "207") (name "unconnected-(P2-ID-Pad4)") (class "Default")
      (node (ref "P2") (pin "4") (pinfunction "ID_4") (pintype "passive"))
    )
  )
)
